# boost-dc-dc.net
KiCad netlist of a schematic drawn in Altium Designer
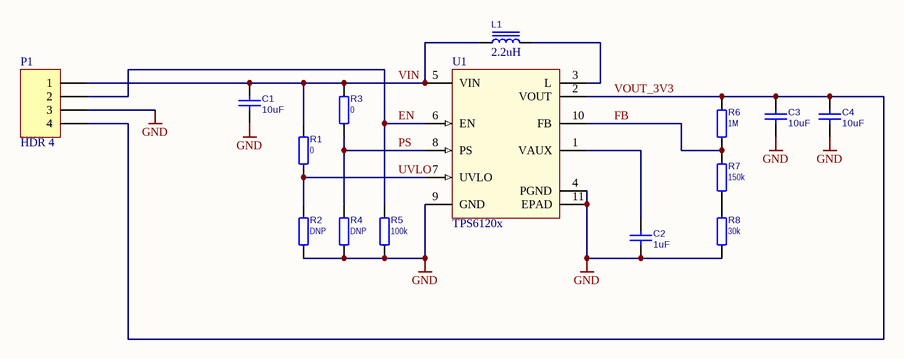
[diagram p0: boost-dc-dc.SchDoc]

(export (version "E")
  (design (tool "Eeschema 10.0.6"))
  (components
    (comp (ref "C1")
      (value "10uF")
      (footprint "Capacitors:C0805")
      (description "CAP_NPOL")
      (libsource (lib "capacitors") (part "CAP_NPOL"))
    )
    (comp (ref "C2")
      (value "1uF")
      (footprint "Capacitors:C0603")
      (description "CAP_NPOL")
      (libsource (lib "capacitors") (part "CAP_NPOL"))
    )
    (comp (ref "C3")
      (value "10uF")
      (footprint "Capacitors:C0805")
      (description "CAP_NPOL")
      (libsource (lib "capacitors") (part "CAP_NPOL"))
    )
    (comp (ref "C4")
      (value "10uF")
      (footprint "Capacitors:C0805")
      (description "CAP_NPOL")
      (libsource (lib "capacitors") (part "CAP_NPOL"))
    )
    (comp (ref "L1")
      (value "2.2uH")
      (footprint "CDRH4D28")
      (description "IND_W_IRON")
      (libsource (lib "inductors") (part "IND_W_IRON"))
    )
    (comp (ref "P1")
      (value "HDR 4")
      (footprint "PLS-4")
      (description "Header, 4-Pin")
      (fields (field (name "PUBLISHER") "Altium Limited"))
      (libsource (lib "HDR") (part "HDR 4"))
    )
    (comp (ref "R1")
      (value "0")
      (footprint "Resistors:R0603")
      (description "RES")
      (libsource (lib "resistors") (part "RESISTOR"))
    )
    (comp (ref "R2")
      (value "DNP")
      (footprint "Resistors:R0603")
      (description "RES")
      (libsource (lib "resistors") (part "RESISTOR"))
    )
    (comp (ref "R3")
      (value "0")
      (footprint "Resistors:R0603")
      (description "RES")
      (libsource (lib "resistors") (part "RESISTOR"))
    )
    (comp (ref "R4")
      (value "DNP")
      (footprint "Resistors:R0603")
      (description "RES")
      (libsource (lib "resistors") (part "RESISTOR"))
    )
    (comp (ref "R5")
      (value "100k")
      (footprint "Resistors:R0603")
      (description "RES")
      (libsource (lib "resistors") (part "RESISTOR"))
    )
    (comp (ref "R6")
      (value "1M")
      (footprint "Resistors:R0603")
      (description "RES")
      (libsource (lib "resistors") (part "RESISTOR"))
    )
    (comp (ref "R7")
      (value "150k")
      (footprint "Resistors:R0603")
      (description "RES")
      (libsource (lib "resistors") (part "RESISTOR"))
    )
    (comp (ref "R8")
      (value "30k")
      (footprint "Resistors:R0603")
      (description "RES")
      (libsource (lib "resistors") (part "RESISTOR"))
    )
    (comp (ref "U1")
      (value "TPS6120x")
      (footprint "SON:VSON-10-3x3")
      (description "Low Input Voltage Synchronous Boost Converter\r\nWith 1.3-A Switches")
      (libsource (lib "TPS6120x") (part "TPS6120x"))
    )
  )
  (nets
    (net (code "1") (name "/EN") (class "Default")
      (node (ref "P1") (pin "2") (pinfunction "2_2") (pintype "passive"))
      (node (ref "R5") (pin "2") (pinfunction "2_2") (pintype "passive"))
      (node (ref "U1") (pin "6") (pinfunction "EN_6") (pintype "input"))
    )
    (net (code "2") (name "/FB") (class "Default")
      (node (ref "R6") (pin "1") (pinfunction "1_1") (pintype "passive"))
      (node (ref "R7") (pin "2") (pinfunction "2_2") (pintype "passive"))
      (node (ref "U1") (pin "10") (pinfunction "FB_10") (pintype "passive"))
    )
    (net (code "3") (name "/PS") (class "Default")
      (node (ref "R3") (pin "1") (pinfunction "1_1") (pintype "passive"))
      (node (ref "R4") (pin "2") (pinfunction "2_2") (pintype "passive"))
      (node (ref "U1") (pin "8") (pinfunction "PS_8") (pintype "input"))
    )
    (net (code "4") (name "/UVLO") (class "Default")
      (node (ref "R1") (pin "1") (pinfunction "1_1") (pintype "passive"))
      (node (ref "R2") (pin "2") (pinfunction "2_2") (pintype "passive"))
      (node (ref "U1") (pin "7") (pinfunction "UVLO_7") (pintype "input"))
    )
    (net (code "5") (name "/VIN") (class "Default")
      (node (ref "C1") (pin "2") (pinfunction "2_2") (pintype "passive"))
      (node (ref "L1") (pin "1") (pintype "passive"))
      (node (ref "P1") (pin "1") (pinfunction "1_1") (pintype "passive"))
      (node (ref "R1") (pin "2") (pinfunction "2_2") (pintype "passive"))
      (node (ref "R3") (pin "2") (pinfunction "2_2") (pintype "passive"))
      (node (ref "U1") (pin "5") (pinfunction "VIN_5") (pintype "power_in"))
    )
    (net (code "6") (name "/VOUT_3V3") (class "Default")
      (node (ref "C3") (pin "2") (pinfunction "2_2") (pintype "passive"))
      (node (ref "C4") (pin "2") (pinfunction "2_2") (pintype "passive"))
      (node (ref "P1") (pin "4") (pinfunction "4_4") (pintype "passive"))
      (node (ref "R6") (pin "2") (pinfunction "2_2") (pintype "passive"))
      (node (ref "U1") (pin "2") (pinfunction "VOUT_2") (pintype "power_in"))
    )
    (net (code "7") (name "GND") (class "Default")
      (node (ref "C1") (pin "1") (pinfunction "1_1") (pintype "passive"))
      (node (ref "C2") (pin "1") (pinfunction "1_1") (pintype "passive"))
      (node (ref "C3") (pin "1") (pinfunction "1_1") (pintype "passive"))
      (node (ref "C4") (pin "1") (pinfunction "1_1") (pintype "passive"))
      (node (ref "P1") (pin "3") (pinfunction "3_3") (pintype "passive"))
      (node (ref "R2") (pin "1") (pinfunction "1_1") (pintype "passive"))
      (node (ref "R4") (pin "1") (pinfunction "1_1") (pintype "passive"))
      (node (ref "R5") (pin "1") (pinfunction "1_1") (pintype "passive"))
      (node (ref "R8") (pin "1") (pinfunction "1_1") (pintype "passive"))
      (node (ref "U1") (pin "11") (pinfunction "EPAD_11") (pintype "power_in"))
      (node (ref "U1") (pin "4") (pinfunction "PGND_4") (pintype "power_in"))
      (node (ref "U1") (pin "9") (pinfunction "GND_9") (pintype "power_in"))
    )
    (net (code "8") (name "Net-(R7-Pad1)") (class "Default")
      (node (ref "R7") (pin "1") (pinfunction "1_1") (pintype "passive"))
      (node (ref "R8") (pin "2") (pinfunction "2_2") (pintype "passive"))
    )
    (net (code "9") (name "Net-(U1-L)") (class "Default")
      (node (ref "L1") (pin "2") (pintype "passive"))
      (node (ref "U1") (pin "3") (pinfunction "L_3") (pintype "passive"))
    )
    (net (code "10") (name "Net-(U1-VAUX)") (class "Default")
      (node (ref "C2") (pin "2") (pinfunction "2_2") (pintype "passive"))
      (node (ref "U1") (pin "1") (pinfunction "VAUX_1") (pintype "passive"))
    )
  )
)
